# devices.net
KiCad netlist of a schematic drawn in Altium Designer
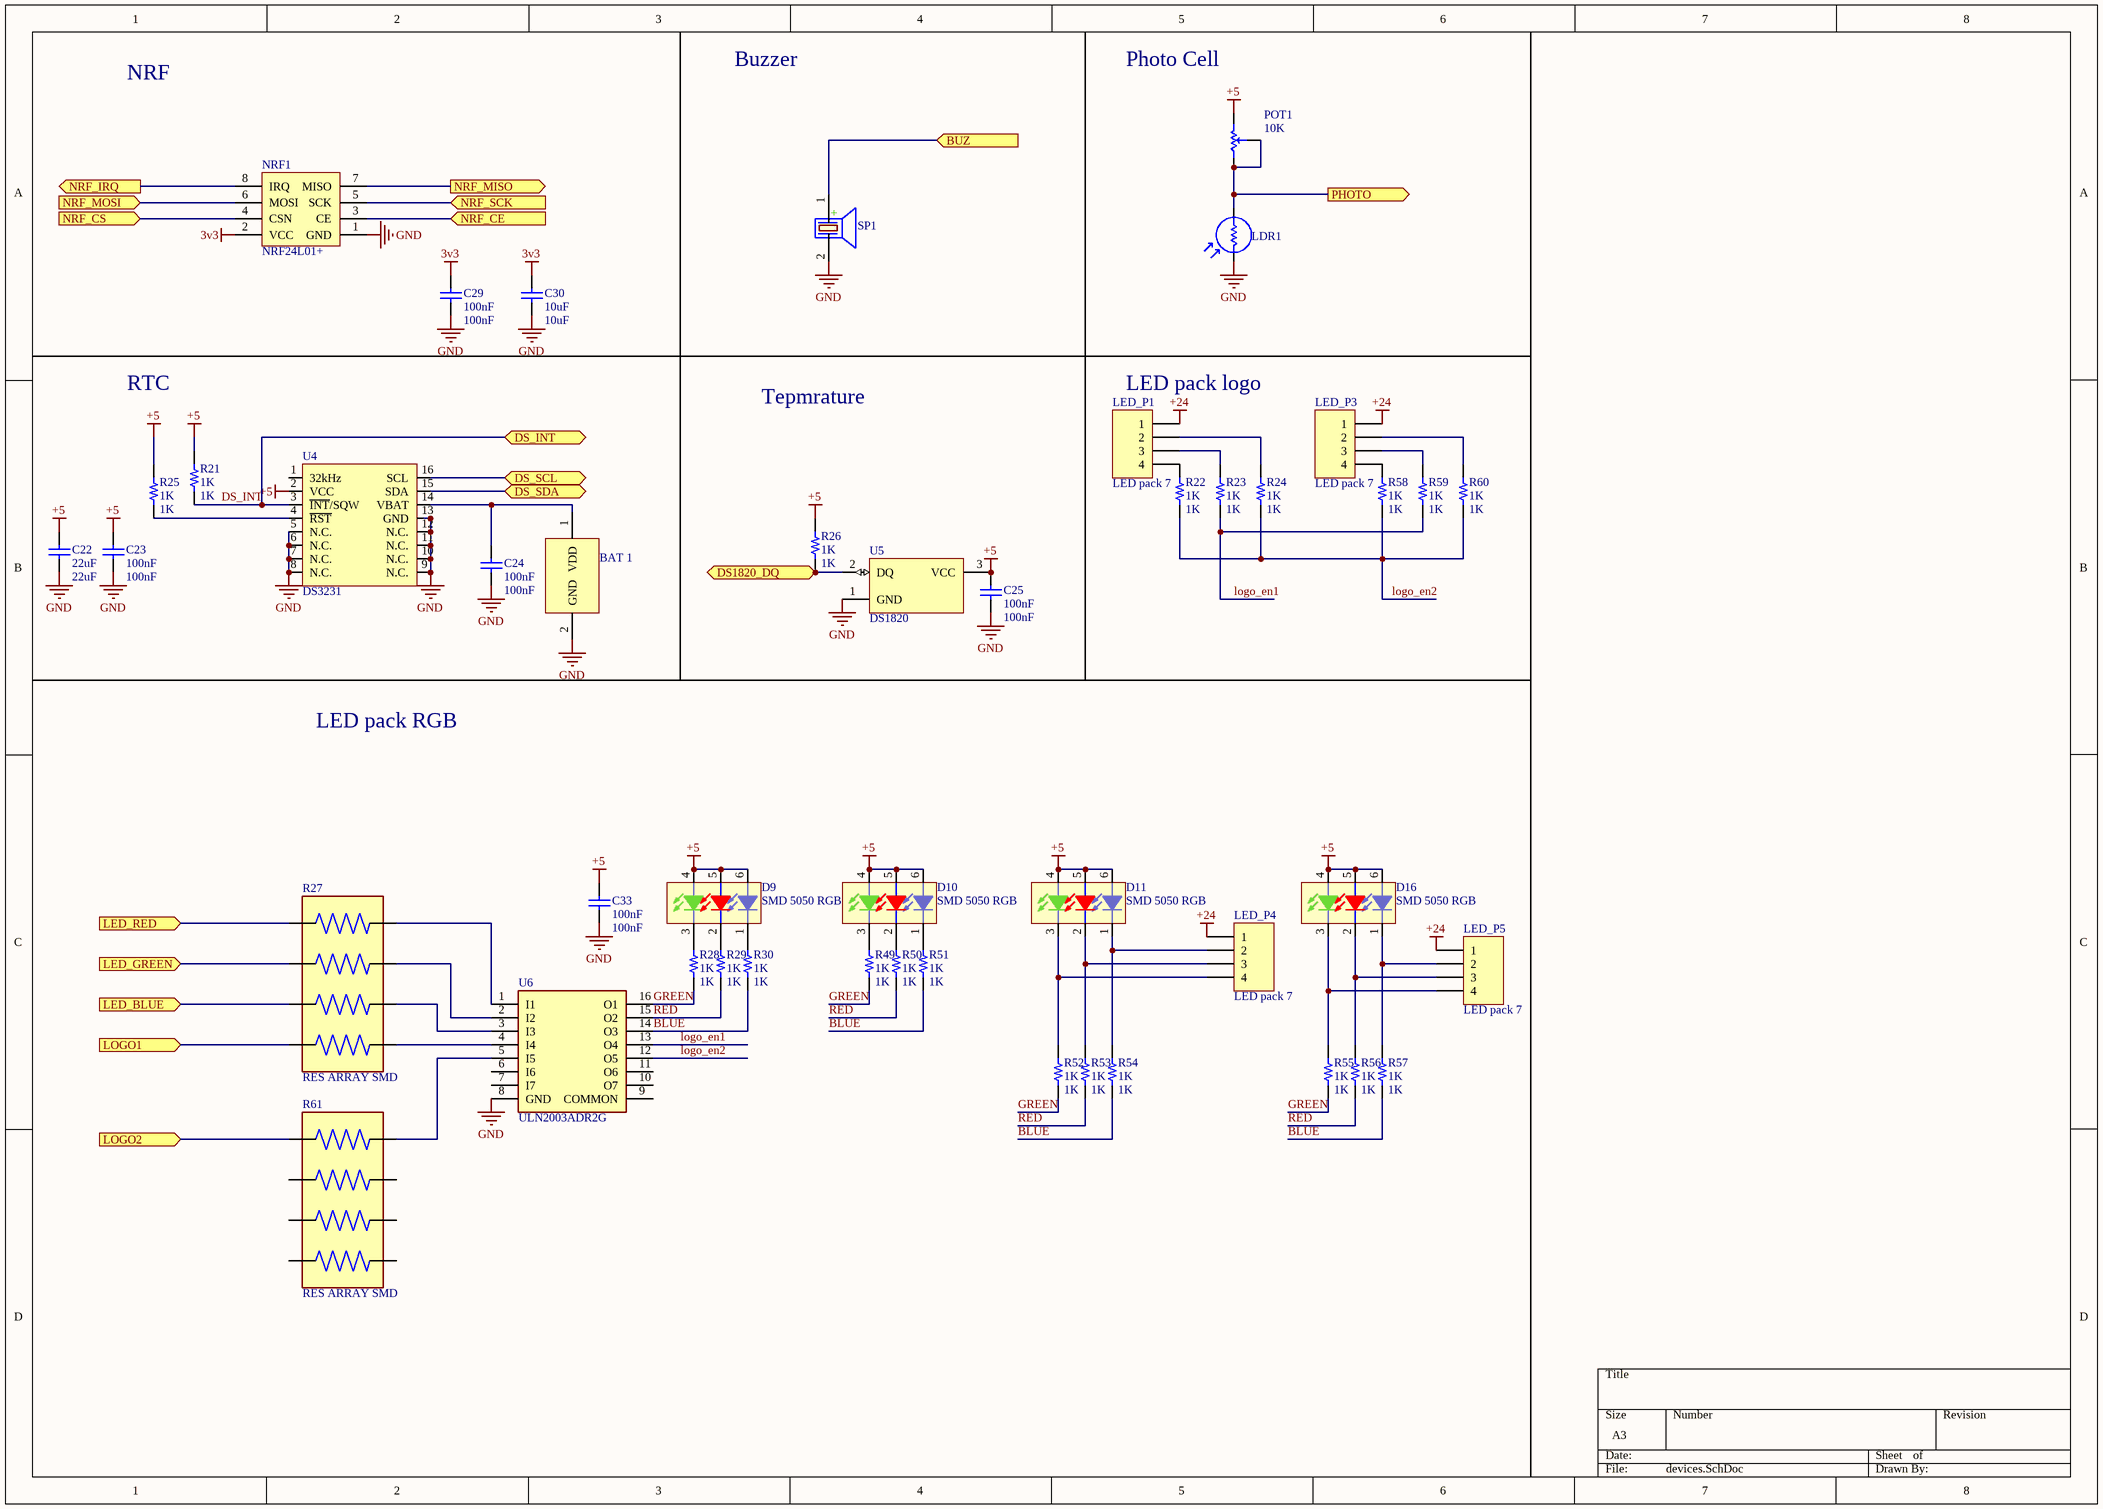
[diagram p0: devices.SchDoc]

(export (version "E")
  (design (tool "Eeschema 10.0.6"))
  (components
    (comp (ref "BAT 1")
      (value "BAT Backup")
      (footprint "BATTERY_coin")
      (description "COIL CELL CR1220")
      (libsource (lib "Altium") (part "BAT Backup"))
    )
    (comp (ref "C22")
      (value "22uF")
      (footprint "0603C")
      (description "CAP SMD 0603")
      (fields (field (name "ALTIUM_VALUE") "22uF") (field (name "PUBLISHER") "Altium Limited"))
      (libsource (lib "Miscellaneous Devices") (part "Cap"))
    )
    (comp (ref "C23")
      (value "100nF")
      (footprint "0603C")
      (description "CAP SMD 0603")
      (fields (field (name "ALTIUM_VALUE") "100nF") (field (name "PUBLISHER") "Altium Limited"))
      (libsource (lib "Miscellaneous Devices") (part "Cap"))
    )
    (comp (ref "C24")
      (value "100nF")
      (footprint "0603C")
      (description "CAP SMD 0603")
      (fields (field (name "ALTIUM_VALUE") "100nF") (field (name "PUBLISHER") "Altium Limited"))
      (libsource (lib "Miscellaneous Devices") (part "Cap"))
    )
    (comp (ref "C25")
      (value "100nF")
      (footprint "0603C")
      (description "CAP SMD 0603")
      (fields (field (name "ALTIUM_VALUE") "100nF") (field (name "PUBLISHER") "Altium Limited"))
      (libsource (lib "Miscellaneous Devices") (part "Cap"))
    )
    (comp (ref "C29")
      (value "100nF")
      (footprint "0603C")
      (description "CAP SMD 0603")
      (fields (field (name "ALTIUM_VALUE") "100nF") (field (name "PUBLISHER") "Altium Limited"))
      (libsource (lib "Miscellaneous Devices") (part "Cap"))
    )
    (comp (ref "C30")
      (value "10uF")
      (footprint "0603C")
      (description "CAP SMD 0603")
      (fields (field (name "ALTIUM_VALUE") "10uF") (field (name "PUBLISHER") "Altium Limited"))
      (libsource (lib "Miscellaneous Devices") (part "Cap"))
    )
    (comp (ref "C33")
      (value "100nF")
      (footprint "0603C")
      (description "CAP SMD 0603")
      (fields (field (name "ALTIUM_VALUE") "100nF") (field (name "PUBLISHER") "Altium Limited"))
      (libsource (lib "Miscellaneous Devices") (part "Cap"))
    )
    (comp (ref "D9")
      (value "5050RGB")
      (footprint "5050 LED package")
      (description "SMD 5050 RGB LED")
      (fields
        (field (name "COMMENT_1") "SMD 5050 RGB")
        (field (name "DESIGNER") "Abbas Basereh")
        (field (name "PUBLISHER") "Abbas Basereh")
      )
      (libsource (lib "Altium (2)") (part "LED SMD 5050 RGB"))
    )
    (comp (ref "D10")
      (value "5050RGB")
      (footprint "5050 LED package")
      (description "SMD 5050 RGB LED")
      (fields
        (field (name "COMMENT_1") "SMD 5050 RGB")
        (field (name "DESIGNER") "Abbas Basereh")
        (field (name "PUBLISHER") "Abbas Basereh")
      )
      (libsource (lib "Altium (2)") (part "LED SMD 5050 RGB"))
    )
    (comp (ref "D11")
      (value "5050RGB")
      (footprint "5050 LED package")
      (description "SMD 5050 RGB LED")
      (fields
        (field (name "COMMENT_1") "SMD 5050 RGB")
        (field (name "DESIGNER") "Abbas Basereh")
        (field (name "PUBLISHER") "Abbas Basereh")
      )
      (libsource (lib "Altium (2)") (part "LED SMD 5050 RGB"))
    )
    (comp (ref "D16")
      (value "5050RGB")
      (footprint "5050 LED package")
      (description "SMD 5050 RGB LED")
      (fields
        (field (name "COMMENT_1") "SMD 5050 RGB")
        (field (name "DESIGNER") "Abbas Basereh")
        (field (name "PUBLISHER") "Abbas Basereh")
      )
      (libsource (lib "Altium (2)") (part "LED SMD 5050 RGB"))
    )
    (comp (ref "LDR1")
      (value "PhotoCell-5mm")
      (footprint "PhotoCell")
      (description "Photo Cell- Variable Resistor With Light")
      (fields (field (name "DESIGNER") "Saeid Jorablo"))
      (libsource (lib "Altium") (part "LDR"))
    )
    (comp (ref "LED_P1")
      (value "LED pack 7")
      (footprint "LED_PAKC_7")
      (description "7led-red white LED pack")
      (fields (field (name "PUBLISHER") "Altium Limited"))
      (libsource (lib "") (part "Header 4_1"))
    )
    (comp (ref "LED_P3")
      (value "LED pack 7")
      (footprint "LED_PAKC_7")
      (description "7led-red white LED pack")
      (fields (field (name "PUBLISHER") "Altium Limited"))
      (libsource (lib "") (part "Header 4_1"))
    )
    (comp (ref "LED_P4")
      (value "LED pack 7")
      (footprint "LED_PAKC_7")
      (description "7led-red white LED pack")
      (fields (field (name "PUBLISHER") "Altium Limited"))
      (libsource (lib "Altium") (part "Header 4"))
    )
    (comp (ref "LED_P5")
      (value "LED pack 7")
      (footprint "LED_PAKC_7")
      (description "7led-red white LED pack")
      (fields (field (name "PUBLISHER") "Altium Limited"))
      (libsource (lib "Altium") (part "Header 4"))
    )
    (comp (ref "NRF1")
      (value "NRF24L01+")
      (footprint "NRF24L01P")
      (description "NRF Module")
      (libsource (lib "Altium") (part "NRF24L01P"))
    )
    (comp (ref "POT1")
      (value "10K")
      (footprint "POT 2")
      (description "Variable Resistor")
      (libsource (lib "Altium (2)") (part "POT"))
    )
    (comp (ref "R21")
      (value "1K")
      (footprint "0603R")
      (description "RES SMD 0603")
      (fields (field (name "PART NUMBER") "RCS0805100KFKEA") (field (name "ALTIUM_VALUE") "1K"))
      (libsource (lib "lamp control-ver2") (part "Resistor"))
    )
    (comp (ref "R22")
      (value "1K")
      (footprint "RES1812")
      (description "RES SMD 1812")
      (fields (field (name "PART NUMBER") "RCS0805100KFKEA") (field (name "ALTIUM_VALUE") "1K"))
      (libsource (lib "lamp control-ver2") (part "Resistor"))
    )
    (comp (ref "R23")
      (value "1K")
      (footprint "RES1812")
      (description "RES SMD 1812")
      (fields (field (name "PART NUMBER") "RCS0805100KFKEA") (field (name "ALTIUM_VALUE") "1K"))
      (libsource (lib "lamp control-ver2") (part "Resistor"))
    )
    (comp (ref "R24")
      (value "1K")
      (footprint "RES1812")
      (description "RES SMD 1812")
      (fields (field (name "PART NUMBER") "RCS0805100KFKEA") (field (name "ALTIUM_VALUE") "1K"))
      (libsource (lib "lamp control-ver2") (part "Resistor"))
    )
    (comp (ref "R25")
      (value "1K")
      (footprint "0603R")
      (description "RES SMD 0603")
      (fields (field (name "PART NUMBER") "RCS0805100KFKEA") (field (name "ALTIUM_VALUE") "1K"))
      (libsource (lib "lamp control-ver2") (part "Resistor"))
    )
    (comp (ref "R26")
      (value "1K")
      (footprint "0603R")
      (description "RES SMD 0603")
      (fields (field (name "PART NUMBER") "RCS0805100KFKEA") (field (name "ALTIUM_VALUE") "1K"))
      (libsource (lib "lamp control-ver2") (part "Resistor"))
    )
    (comp (ref "R27")
      (value "RES ARRAY SMD")
      (footprint "RESCAXE80P320X160X70-8N")
      (description "RES Array 0603-4x 100 to 200 OHM")
      (fields (field (name "MF") "Yageo") (field (name "MP") "YC164-JR-07330RL"))
      (libsource (lib "YC164-JR-07330RL") (part "YC164-JR-07330RL"))
    )
    (comp (ref "R28")
      (value "1K")
      (footprint "0603R")
      (description "RES SMD 0603")
      (fields (field (name "PART NUMBER") "RCS0805100KFKEA") (field (name "ALTIUM_VALUE") "1K"))
      (libsource (lib "lamp control-ver2") (part "Resistor"))
    )
    (comp (ref "R29")
      (value "1K")
      (footprint "0603R")
      (description "RES SMD 0603")
      (fields (field (name "PART NUMBER") "RCS0805100KFKEA") (field (name "ALTIUM_VALUE") "1K"))
      (libsource (lib "lamp control-ver2") (part "Resistor"))
    )
    (comp (ref "R30")
      (value "1K")
      (footprint "0603R")
      (description "RES SMD 0603")
      (fields (field (name "PART NUMBER") "RCS0805100KFKEA") (field (name "ALTIUM_VALUE") "1K"))
      (libsource (lib "lamp control-ver2") (part "Resistor"))
    )
    (comp (ref "R49")
      (value "1K")
      (footprint "0603R")
      (description "RES SMD 0603")
      (fields (field (name "PART NUMBER") "RCS0805100KFKEA") (field (name "ALTIUM_VALUE") "1K"))
      (libsource (lib "lamp control-ver2") (part "Resistor"))
    )
    (comp (ref "R50")
      (value "1K")
      (footprint "0603R")
      (description "RES SMD 0603")
      (fields (field (name "PART NUMBER") "RCS0805100KFKEA") (field (name "ALTIUM_VALUE") "1K"))
      (libsource (lib "lamp control-ver2") (part "Resistor"))
    )
    (comp (ref "R51")
      (value "1K")
      (footprint "0603R")
      (description "RES SMD 0603")
      (fields (field (name "PART NUMBER") "RCS0805100KFKEA") (field (name "ALTIUM_VALUE") "1K"))
      (libsource (lib "lamp control-ver2") (part "Resistor"))
    )
    (comp (ref "R52")
      (value "1K")
      (footprint "RES1812")
      (description "RES SMD 1812")
      (fields (field (name "PART NUMBER") "RCS0805100KFKEA") (field (name "ALTIUM_VALUE") "1K"))
      (libsource (lib "lamp control-ver2") (part "Resistor"))
    )
    (comp (ref "R53")
      (value "1K")
      (footprint "RES1812")
      (description "RES SMD 1812")
      (fields (field (name "PART NUMBER") "RCS0805100KFKEA") (field (name "ALTIUM_VALUE") "1K"))
      (libsource (lib "lamp control-ver2") (part "Resistor"))
    )
    (comp (ref "R54")
      (value "1K")
      (footprint "RES1812")
      (description "RES SMD 1812")
      (fields (field (name "PART NUMBER") "RCS0805100KFKEA") (field (name "ALTIUM_VALUE") "1K"))
      (libsource (lib "lamp control-ver2") (part "Resistor"))
    )
    (comp (ref "R55")
      (value "1K")
      (footprint "RES1812")
      (description "RES SMD 1812")
      (fields (field (name "PART NUMBER") "RCS0805100KFKEA") (field (name "ALTIUM_VALUE") "1K"))
      (libsource (lib "lamp control-ver2") (part "Resistor"))
    )
    (comp (ref "R56")
      (value "1K")
      (footprint "RES1812")
      (description "RES SMD 1812")
      (fields (field (name "PART NUMBER") "RCS0805100KFKEA") (field (name "ALTIUM_VALUE") "1K"))
      (libsource (lib "lamp control-ver2") (part "Resistor"))
    )
    (comp (ref "R57")
      (value "1K")
      (footprint "RES1812")
      (description "RES SMD 1812")
      (fields (field (name "PART NUMBER") "RCS0805100KFKEA") (field (name "ALTIUM_VALUE") "1K"))
      (libsource (lib "lamp control-ver2") (part "Resistor"))
    )
    (comp (ref "R58")
      (value "1K")
      (footprint "RES1812")
      (description "RES SMD 1812")
      (fields (field (name "PART NUMBER") "RCS0805100KFKEA") (field (name "ALTIUM_VALUE") "1K"))
      (libsource (lib "lamp control-ver2") (part "Resistor"))
    )
    (comp (ref "R59")
      (value "1K")
      (footprint "RES1812")
      (description "RES SMD 1812")
      (fields (field (name "PART NUMBER") "RCS0805100KFKEA") (field (name "ALTIUM_VALUE") "1K"))
      (libsource (lib "lamp control-ver2") (part "Resistor"))
    )
    (comp (ref "R60")
      (value "1K")
      (footprint "RES1812")
      (description "RES SMD 1812")
      (fields (field (name "PART NUMBER") "RCS0805100KFKEA") (field (name "ALTIUM_VALUE") "1K"))
      (libsource (lib "lamp control-ver2") (part "Resistor"))
    )
    (comp (ref "R61")
      (value "RES ARRAY SMD")
      (footprint "RESCAXE80P320X160X70-8N")
      (description "RES Array 0603-4x 100 to 200 OHM")
      (fields (field (name "MF") "Yageo") (field (name "MP") "YC164-JR-07330RL"))
      (libsource (lib "YC164-JR-07330RL") (part "YC164-JR-07330RL"))
    )
    (comp (ref "SP1")
      (value "BUZZER")
      (footprint "BUZZER 7.62mm DC")
      (description "PIEZO BUZZER 5VOLTS")
      (fields (field (name "DESIGNER") "Abbas Basereh") (field (name "PUBLISHER") "Abbas Basereh"))
      (libsource (lib "Altium (2)") (part "PIEZO BUZZER"))
    )
    (comp (ref "U4")
      (value "DS3231")
      (footprint "SO-16W")
      (description "DS3231 RTC")
      (libsource (lib "ZetaBoard_Lib") (part "DS3231"))
    )
    (comp (ref "U5")
      (value "DS1820")
      (footprint "DS1820")
      (description "1-Wire Digital Thermometer")
      (fields (field (name "PUBLISHER") "Altium Limited"))
      (libsource (lib "PicPars.com_usefully_Library") (part "DS1820"))
    )
    (comp (ref "U6")
      (value "ULN2003ADR2G")
      (footprint "SOIC127P600X175-16N")
      (description "ULN2003 SMD")
      (fields (field (name "MOUSER PART NUMBER") "863-ULN2003ADR2G"))
      (libsource (lib "*") (part "ULN2003ADR2G"))
    )
  )
  (nets
    (net (code "1") (name "+5") (class "Default")
      (node (ref "C22") (pin "2") (pinfunction "2_2") (pintype "passive"))
      (node (ref "C23") (pin "2") (pinfunction "2_2") (pintype "passive"))
      (node (ref "C25") (pin "2") (pinfunction "2_2") (pintype "passive"))
      (node (ref "C33") (pin "2") (pinfunction "2_2") (pintype "passive"))
      (node (ref "D10") (pin "4") (pinfunction "4_4") (pintype "passive"))
      (node (ref "D10") (pin "5") (pinfunction "5_5") (pintype "passive"))
      (node (ref "D10") (pin "6") (pinfunction "6_6") (pintype "passive"))
      (node (ref "D11") (pin "4") (pinfunction "4_4") (pintype "passive"))
      (node (ref "D11") (pin "5") (pinfunction "5_5") (pintype "passive"))
      (node (ref "D11") (pin "6") (pinfunction "6_6") (pintype "passive"))
      (node (ref "D16") (pin "4") (pinfunction "4_4") (pintype "passive"))
      (node (ref "D16") (pin "5") (pinfunction "5_5") (pintype "passive"))
      (node (ref "D16") (pin "6") (pinfunction "6_6") (pintype "passive"))
      (node (ref "D9") (pin "4") (pinfunction "4_4") (pintype "passive"))
      (node (ref "D9") (pin "5") (pinfunction "5_5") (pintype "passive"))
      (node (ref "D9") (pin "6") (pinfunction "6_6") (pintype "passive"))
      (node (ref "POT1") (pin "2") (pinfunction "CW_2") (pintype "passive"))
      (node (ref "R21") (pin "2") (pinfunction "2_2") (pintype "passive"))
      (node (ref "R25") (pin "2") (pinfunction "2_2") (pintype "passive"))
      (node (ref "R26") (pin "2") (pinfunction "2_2") (pintype "passive"))
      (node (ref "U4") (pin "2") (pinfunction "VCC_2") (pintype "passive"))
      (node (ref "U5") (pin "3") (pinfunction "VCC_3") (pintype "power_in"))
    )
    (net (code "2") (name "+24") (class "Default")
      (node (ref "LED_P1") (pin "1") (pinfunction "1_1") (pintype "passive"))
      (node (ref "LED_P3") (pin "1") (pinfunction "1_1") (pintype "passive"))
      (node (ref "LED_P4") (pin "1") (pinfunction "1_1") (pintype "passive"))
      (node (ref "LED_P5") (pin "1") (pinfunction "1_1") (pintype "passive"))
    )
    (net (code "3") (name "/BLUE") (class "Default")
      (node (ref "R30") (pin "1") (pinfunction "1_1") (pintype "passive"))
      (node (ref "R51") (pin "1") (pinfunction "1_1") (pintype "passive"))
      (node (ref "R54") (pin "1") (pinfunction "1_1") (pintype "passive"))
      (node (ref "R57") (pin "1") (pinfunction "1_1") (pintype "passive"))
      (node (ref "U6") (pin "14") (pinfunction "O3_14") (pintype "passive"))
    )
    (net (code "4") (name "/BUZ") (class "Default")
      (node (ref "SP1") (pin "1") (pinfunction "+_1") (pintype "passive"))
    )
    (net (code "5") (name "/DS1820_DQ") (class "Default")
      (node (ref "R26") (pin "1") (pinfunction "1_1") (pintype "passive"))
      (node (ref "U5") (pin "2") (pinfunction "DQ_2") (pintype "bidirectional"))
    )
    (net (code "6") (name "/DS_INT") (class "Default")
      (node (ref "R21") (pin "1") (pinfunction "1_1") (pintype "passive"))
      (node (ref "U4") (pin "3") (pinfunction "~{INT}/SQW_3") (pintype "passive"))
    )
    (net (code "7") (name "/DS_SCL") (class "Default")
      (node (ref "U4") (pin "16") (pinfunction "SCL_16") (pintype "passive"))
    )
    (net (code "8") (name "/DS_SDA") (class "Default")
      (node (ref "U4") (pin "15") (pinfunction "SDA_15") (pintype "passive"))
    )
    (net (code "9") (name "/GREEN") (class "Default")
      (node (ref "R28") (pin "1") (pinfunction "1_1") (pintype "passive"))
      (node (ref "R49") (pin "1") (pinfunction "1_1") (pintype "passive"))
      (node (ref "R52") (pin "1") (pinfunction "1_1") (pintype "passive"))
      (node (ref "R55") (pin "1") (pinfunction "1_1") (pintype "passive"))
      (node (ref "U6") (pin "16") (pinfunction "O1_16") (pintype "passive"))
    )
    (net (code "10") (name "/LED_BLUE") (class "Default")
      (node (ref "R27") (pin "3") (pinfunction "3_3") (pintype "passive"))
    )
    (net (code "11") (name "/LED_GREEN") (class "Default")
      (node (ref "R27") (pin "2") (pinfunction "2_2") (pintype "passive"))
    )
    (net (code "12") (name "/LED_RED") (class "Default")
      (node (ref "R27") (pin "1") (pinfunction "1_1") (pintype "passive"))
    )
    (net (code "13") (name "/LOGO1") (class "Default")
      (node (ref "R27") (pin "4") (pinfunction "4_4") (pintype "passive"))
    )
    (net (code "14") (name "/LOGO2") (class "Default")
      (node (ref "R61") (pin "1") (pinfunction "1_1") (pintype "passive"))
    )
    (net (code "15") (name "/NRF_CE") (class "Default")
      (node (ref "NRF1") (pin "3") (pinfunction "CE_3") (pintype "passive"))
    )
    (net (code "16") (name "/NRF_CS") (class "Default")
      (node (ref "NRF1") (pin "4") (pinfunction "CSN_4") (pintype "passive"))
    )
    (net (code "17") (name "/NRF_IRQ") (class "Default")
      (node (ref "NRF1") (pin "8") (pinfunction "IRQ_8") (pintype "passive"))
    )
    (net (code "18") (name "/NRF_MISO") (class "Default")
      (node (ref "NRF1") (pin "7") (pinfunction "MISO_7") (pintype "passive"))
    )
    (net (code "19") (name "/NRF_MOSI") (class "Default")
      (node (ref "NRF1") (pin "6") (pinfunction "MOSI_6") (pintype "passive"))
    )
    (net (code "20") (name "/NRF_SCK") (class "Default")
      (node (ref "NRF1") (pin "5") (pinfunction "SCK_5") (pintype "passive"))
    )
    (net (code "21") (name "/PHOTO") (class "Default")
      (node (ref "LDR1") (pin "2") (pintype "passive"))
      (node (ref "POT1") (pin "1") (pinfunction "CCW_1") (pintype "passive"))
      (node (ref "POT1") (pin "3") (pinfunction "SetPoint_3") (pintype "passive"))
    )
    (net (code "22") (name "/RED") (class "Default")
      (node (ref "R29") (pin "1") (pinfunction "1_1") (pintype "passive"))
      (node (ref "R50") (pin "1") (pinfunction "1_1") (pintype "passive"))
      (node (ref "R53") (pin "1") (pinfunction "1_1") (pintype "passive"))
      (node (ref "R56") (pin "1") (pinfunction "1_1") (pintype "passive"))
      (node (ref "U6") (pin "15") (pinfunction "O2_15") (pintype "passive"))
    )
    (net (code "23") (name "/logo_en1") (class "Default")
      (node (ref "R23") (pin "1") (pinfunction "1_1") (pintype "passive"))
      (node (ref "R59") (pin "1") (pinfunction "1_1") (pintype "passive"))
      (node (ref "U6") (pin "13") (pinfunction "O4_13") (pintype "passive"))
    )
    (net (code "24") (name "/logo_en2") (class "Default")
      (node (ref "R22") (pin "2") (pinfunction "2_2") (pintype "passive"))
      (node (ref "R24") (pin "1") (pinfunction "1_1") (pintype "passive"))
      (node (ref "R58") (pin "2") (pinfunction "2_2") (pintype "passive"))
      (node (ref "R60") (pin "1") (pinfunction "1_1") (pintype "passive"))
      (node (ref "U6") (pin "12") (pinfunction "O5_12") (pintype "passive"))
    )
    (net (code "25") (name "3v3") (class "Default")
      (node (ref "C29") (pin "2") (pinfunction "2_2") (pintype "passive"))
      (node (ref "C30") (pin "2") (pinfunction "2_2") (pintype "passive"))
      (node (ref "NRF1") (pin "2") (pinfunction "VCC_2") (pintype "passive"))
    )
    (net (code "26") (name "GND") (class "Default")
      (node (ref "BAT 1") (pin "2") (pinfunction "GND_2") (pintype "passive"))
      (node (ref "C22") (pin "1") (pinfunction "1_1") (pintype "passive"))
      (node (ref "C23") (pin "1") (pinfunction "1_1") (pintype "passive"))
      (node (ref "C24") (pin "1") (pinfunction "1_1") (pintype "passive"))
      (node (ref "C25") (pin "1") (pinfunction "1_1") (pintype "passive"))
      (node (ref "C29") (pin "1") (pinfunction "1_1") (pintype "passive"))
      (node (ref "C30") (pin "1") (pinfunction "1_1") (pintype "passive"))
      (node (ref "C33") (pin "1") (pinfunction "1_1") (pintype "passive"))
      (node (ref "LDR1") (pin "1") (pintype "passive"))
      (node (ref "NRF1") (pin "1") (pinfunction "GND_1") (pintype "passive"))
      (node (ref "SP1") (pin "2") (pinfunction "-_2") (pintype "passive"))
      (node (ref "U4") (pin "10") (pinfunction "N.C._10") (pintype "passive"))
      (node (ref "U4") (pin "11") (pinfunction "N.C._11") (pintype "passive"))
      (node (ref "U4") (pin "12") (pinfunction "N.C._12") (pintype "passive"))
      (node (ref "U4") (pin "13") (pinfunction "GND_13") (pintype "passive"))
      (node (ref "U4") (pin "5") (pinfunction "N.C._5") (pintype "passive"))
      (node (ref "U4") (pin "6") (pinfunction "N.C._6") (pintype "passive"))
      (node (ref "U4") (pin "7") (pinfunction "N.C._7") (pintype "passive"))
      (node (ref "U4") (pin "8") (pinfunction "N.C._8") (pintype "passive"))
      (node (ref "U4") (pin "9") (pinfunction "N.C._9") (pintype "passive"))
      (node (ref "U5") (pin "1") (pinfunction "GND_1") (pintype "power_in"))
      (node (ref "U6") (pin "8") (pinfunction "GND_8") (pintype "passive"))
    )
    (net (code "27") (name "Net-(BAT 1-VDD)") (class "Default")
      (node (ref "BAT 1") (pin "1") (pinfunction "VDD_1") (pintype "passive"))
      (node (ref "C24") (pin "2") (pinfunction "2_2") (pintype "passive"))
      (node (ref "U4") (pin "14") (pinfunction "VBAT_14") (pintype "passive"))
    )
    (net (code "28") (name "Net-(D9-Pad1)") (class "Default")
      (node (ref "D9") (pin "1") (pinfunction "1_1") (pintype "passive"))
      (node (ref "R30") (pin "2") (pinfunction "2_2") (pintype "passive"))
    )
    (net (code "29") (name "Net-(D9-Pad2)") (class "Default")
      (node (ref "D9") (pin "2") (pinfunction "2_2") (pintype "passive"))
      (node (ref "R29") (pin "2") (pinfunction "2_2") (pintype "passive"))
    )
    (net (code "30") (name "Net-(D9-Pad3)") (class "Default")
      (node (ref "D9") (pin "3") (pinfunction "3_3") (pintype "passive"))
      (node (ref "R28") (pin "2") (pinfunction "2_2") (pintype "passive"))
    )
    (net (code "31") (name "Net-(D10-Pad1)") (class "Default")
      (node (ref "D10") (pin "1") (pinfunction "1_1") (pintype "passive"))
      (node (ref "R51") (pin "2") (pinfunction "2_2") (pintype "passive"))
    )
    (net (code "32") (name "Net-(D10-Pad2)") (class "Default")
      (node (ref "D10") (pin "2") (pinfunction "2_2") (pintype "passive"))
      (node (ref "R50") (pin "2") (pinfunction "2_2") (pintype "passive"))
    )
    (net (code "33") (name "Net-(D10-Pad3)") (class "Default")
      (node (ref "D10") (pin "3") (pinfunction "3_3") (pintype "passive"))
      (node (ref "R49") (pin "2") (pinfunction "2_2") (pintype "passive"))
    )
    (net (code "34") (name "Net-(D11-Pad1)") (class "Default")
      (node (ref "D11") (pin "1") (pinfunction "1_1") (pintype "passive"))
      (node (ref "LED_P4") (pin "2") (pinfunction "2_2") (pintype "passive"))
      (node (ref "R54") (pin "2") (pinfunction "2_2") (pintype "passive"))
    )
    (net (code "35") (name "Net-(D11-Pad2)") (class "Default")
      (node (ref "D11") (pin "2") (pinfunction "2_2") (pintype "passive"))
      (node (ref "LED_P4") (pin "3") (pinfunction "3_3") (pintype "passive"))
      (node (ref "R53") (pin "2") (pinfunction "2_2") (pintype "passive"))
    )
    (net (code "36") (name "Net-(D11-Pad3)") (class "Default")
      (node (ref "D11") (pin "3") (pinfunction "3_3") (pintype "passive"))
      (node (ref "LED_P4") (pin "4") (pinfunction "4_4") (pintype "passive"))
      (node (ref "R52") (pin "2") (pinfunction "2_2") (pintype "passive"))
    )
    (net (code "37") (name "Net-(D16-Pad1)") (class "Default")
      (node (ref "D16") (pin "1") (pinfunction "1_1") (pintype "passive"))
      (node (ref "LED_P5") (pin "2") (pinfunction "2_2") (pintype "passive"))
      (node (ref "R57") (pin "2") (pinfunction "2_2") (pintype "passive"))
    )
    (net (code "38") (name "Net-(D16-Pad2)") (class "Default")
      (node (ref "D16") (pin "2") (pinfunction "2_2") (pintype "passive"))
      (node (ref "LED_P5") (pin "3") (pinfunction "3_3") (pintype "passive"))
      (node (ref "R56") (pin "2") (pinfunction "2_2") (pintype "passive"))
    )
    (net (code "39") (name "Net-(D16-Pad3)") (class "Default")
      (node (ref "D16") (pin "3") (pinfunction "3_3") (pintype "passive"))
      (node (ref "LED_P5") (pin "4") (pinfunction "4_4") (pintype "passive"))
      (node (ref "R55") (pin "2") (pinfunction "2_2") (pintype "passive"))
    )
    (net (code "40") (name "Net-(LED_P1-Pad2)") (class "Default")
      (node (ref "LED_P1") (pin "2") (pinfunction "2_2") (pintype "passive"))
      (node (ref "R24") (pin "2") (pinfunction "2_2") (pintype "passive"))
    )
    (net (code "41") (name "Net-(LED_P1-Pad3)") (class "Default")
      (node (ref "LED_P1") (pin "3") (pinfunction "3_3") (pintype "passive"))
      (node (ref "R23") (pin "2") (pinfunction "2_2") (pintype "passive"))
    )
    (net (code "42") (name "Net-(LED_P1-Pad4)") (class "Default")
      (node (ref "LED_P1") (pin "4") (pinfunction "4_4") (pintype "passive"))
      (node (ref "R22") (pin "1") (pinfunction "1_1") (pintype "passive"))
    )
    (net (code "43") (name "Net-(LED_P3-Pad2)") (class "Default")
      (node (ref "LED_P3") (pin "2") (pinfunction "2_2") (pintype "passive"))
      (node (ref "R60") (pin "2") (pinfunction "2_2") (pintype "passive"))
    )
    (net (code "44") (name "Net-(LED_P3-Pad3)") (class "Default")
      (node (ref "LED_P3") (pin "3") (pinfunction "3_3") (pintype "passive"))
      (node (ref "R59") (pin "2") (pinfunction "2_2") (pintype "passive"))
    )
    (net (code "45") (name "Net-(LED_P3-Pad4)") (class "Default")
      (node (ref "LED_P3") (pin "4") (pinfunction "4_4") (pintype "passive"))
      (node (ref "R58") (pin "1") (pinfunction "1_1") (pintype "passive"))
    )
    (net (code "46") (name "Net-(U4-~{RST})") (class "Default")
      (node (ref "R25") (pin "1") (pinfunction "1_1") (pintype "passive"))
      (node (ref "U4") (pin "4") (pinfunction "~{RST}_4") (pintype "passive"))
    )
    (net (code "47") (name "Net-(U6-I1)") (class "Default")
      (node (ref "R27") (pin "8") (pinfunction "8_8") (pintype "passive"))
      (node (ref "U6") (pin "1") (pinfunction "I1_1") (pintype "passive"))
    )
    (net (code "48") (name "Net-(U6-I2)") (class "Default")
      (node (ref "R27") (pin "7") (pinfunction "7_7") (pintype "passive"))
      (node (ref "U6") (pin "2") (pinfunction "I2_2") (pintype "passive"))
    )
    (net (code "49") (name "Net-(U6-I3)") (class "Default")
      (node (ref "R27") (pin "6") (pinfunction "6_6") (pintype "passive"))
      (node (ref "U6") (pin "3") (pinfunction "I3_3") (pintype "passive"))
    )
    (net (code "50") (name "Net-(U6-I4)") (class "Default")
      (node (ref "R27") (pin "5") (pinfunction "5_5") (pintype "passive"))
      (node (ref "U6") (pin "4") (pinfunction "I4_4") (pintype "passive"))
    )
    (net (code "51") (name "Net-(U6-I5)") (class "Default")
      (node (ref "R61") (pin "8") (pinfunction "8_8") (pintype "passive"))
      (node (ref "U6") (pin "5") (pinfunction "I5_5") (pintype "passive"))
    )
    (net (code "52") (name "unconnected-(R61-Pad2)") (class "Default")
      (node (ref "R61") (pin "2") (pinfunction "2_2") (pintype "passive"))
    )
    (net (code "53") (name "unconnected-(R61-Pad3)") (class "Default")
      (node (ref "R61") (pin "3") (pinfunction "3_3") (pintype "passive"))
    )
    (net (code "54") (name "unconnected-(R61-Pad4)") (class "Default")
      (node (ref "R61") (pin "4") (pinfunction "4_4") (pintype "passive"))
    )
    (net (code "55") (name "unconnected-(R61-Pad5)") (class "Default")
      (node (ref "R61") (pin "5") (pinfunction "5_5") (pintype "passive"))
    )
    (net (code "56") (name "unconnected-(R61-Pad6)") (class "Default")
      (node (ref "R61") (pin "6") (pinfunction "6_6") (pintype "passive"))
    )
    (net (code "57") (name "unconnected-(R61-Pad7)") (class "Default")
      (node (ref "R61") (pin "7") (pinfunction "7_7") (pintype "passive"))
    )
    (net (code "58") (name "unconnected-(U4-32kHz-Pad1)") (class "Default")
      (node (ref "U4") (pin "1") (pinfunction "32kHz_1") (pintype "passive"))
    )
    (net (code "59") (name "unconnected-(U6-COMMON-Pad9)") (class "Default")
      (node (ref "U6") (pin "9") (pinfunction "COMMON_9") (pintype "passive"))
    )
    (net (code "60") (name "unconnected-(U6-I6-Pad6)") (class "Default")
      (node (ref "U6") (pin "6") (pinfunction "I6_6") (pintype "passive"))
    )
    (net (code "61") (name "unconnected-(U6-I7-Pad7)") (class "Default")
      (node (ref "U6") (pin "7") (pinfunction "I7_7") (pintype "passive"))
    )
    (net (code "62") (name "unconnected-(U6-O6-Pad11)") (class "Default")
      (node (ref "U6") (pin "11") (pinfunction "O6_11") (pintype "passive"))
    )
    (net (code "63") (name "unconnected-(U6-O7-Pad10)") (class "Default")
      (node (ref "U6") (pin "10") (pinfunction "O7_10") (pintype "passive"))
    )
  )
)
